# MurataBreakout_rev1.net
KiCad netlist of a schematic drawn in EAGLE
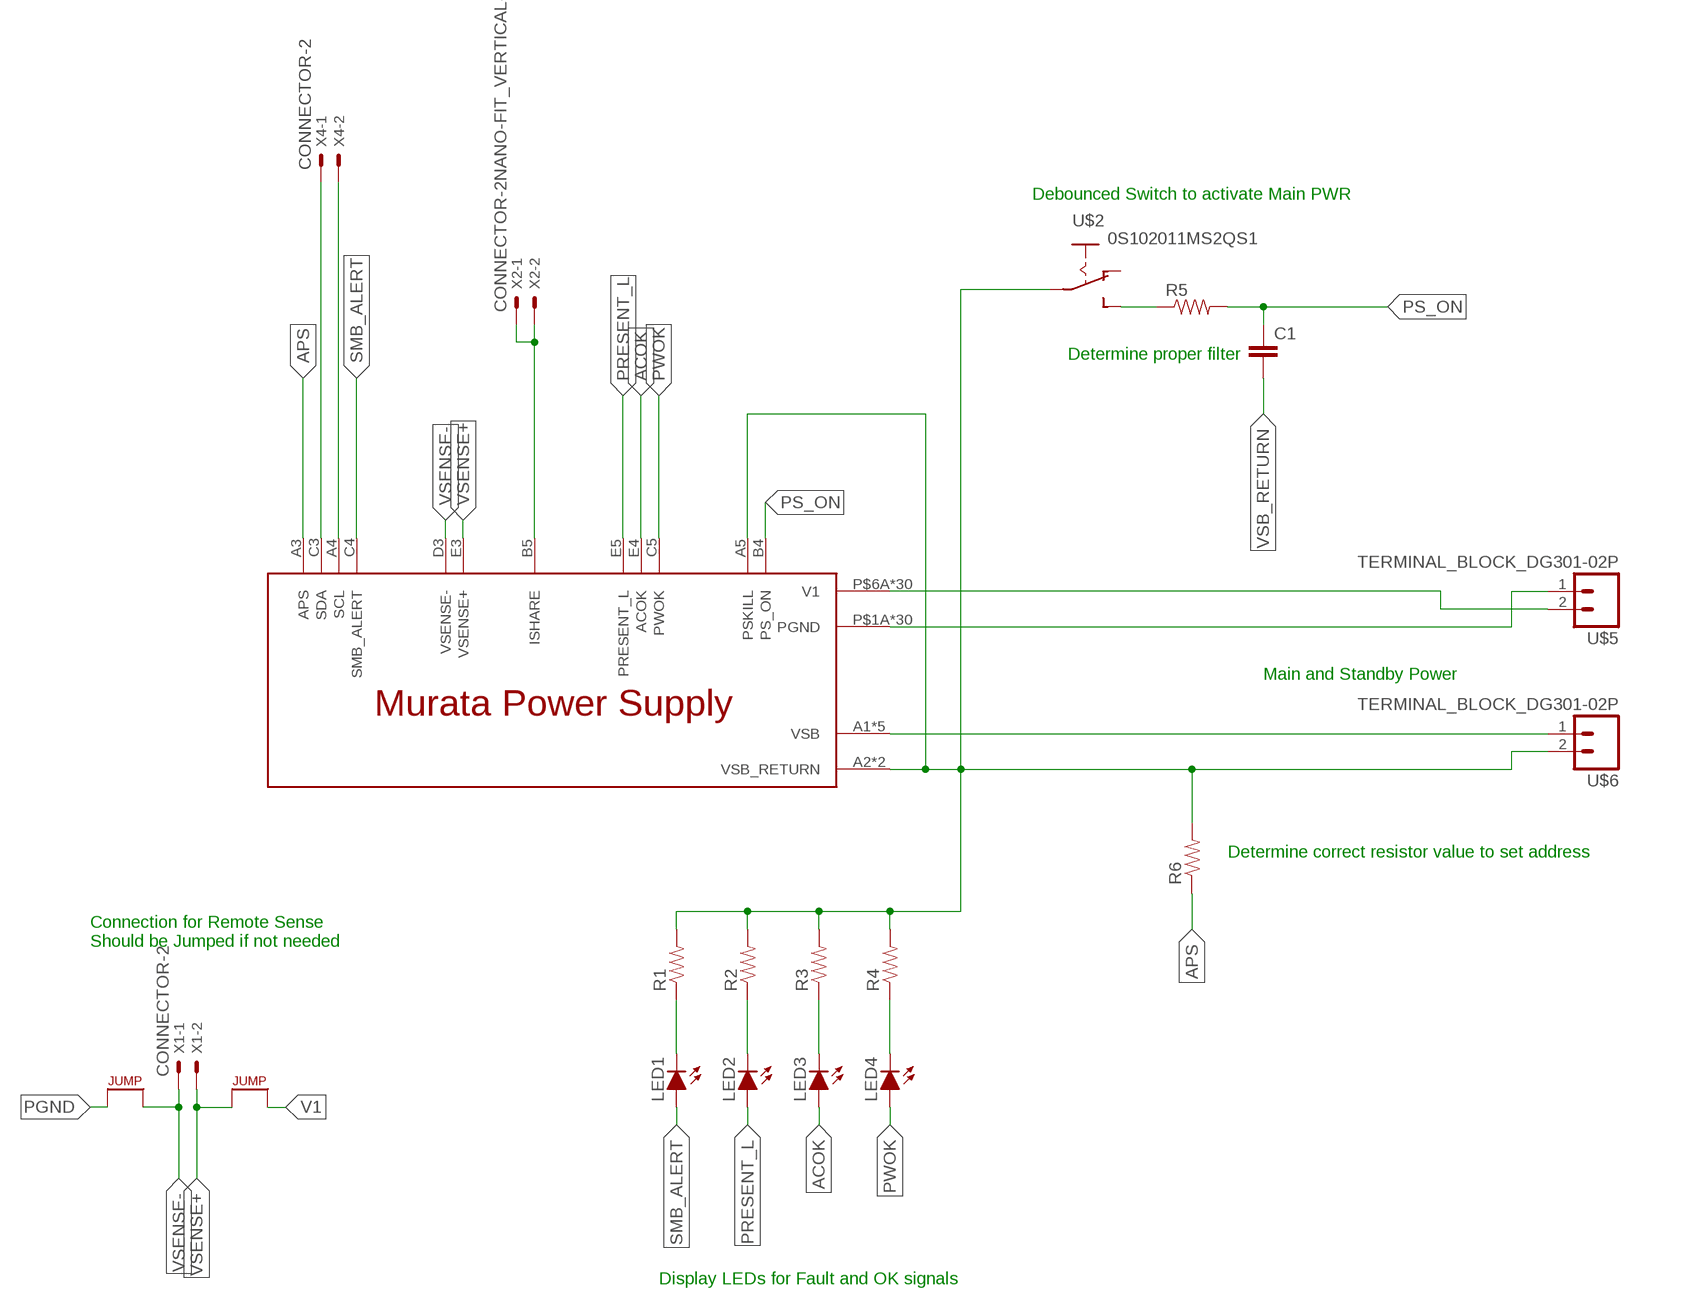
[diagram p0: schematic, sheet 1]

(export (version "E")
  (design (tool "Eeschema 10.0.6"))
  (components
    (comp (ref "C1")
      (value "CAP0805")
      (footprint "eagle-import:0805")
      (libsource (lib "eagle-import") (part "CAP0805"))
    )
    (comp (ref "LED1")
      (value "LED-0805")
      (footprint "eagle-import:LED-805")
      (libsource (lib "eagle-import") (part "LED-0805"))
    )
    (comp (ref "LED2")
      (value "LED-0805")
      (footprint "eagle-import:LED-805")
      (libsource (lib "eagle-import") (part "LED-0805"))
    )
    (comp (ref "LED3")
      (value "LED-0805")
      (footprint "eagle-import:LED-805")
      (libsource (lib "eagle-import") (part "LED-0805"))
    )
    (comp (ref "LED4")
      (value "LED-0805")
      (footprint "eagle-import:LED-805")
      (libsource (lib "eagle-import") (part "LED-0805"))
    )
    (comp (ref "R1")
      (value "RESISTOR0805-RES")
      (footprint "eagle-import:0805")
      (libsource (lib "eagle-import") (part "RESISTOR0805-RES"))
    )
    (comp (ref "R2")
      (value "RESISTOR0805-RES")
      (footprint "eagle-import:0805")
      (libsource (lib "eagle-import") (part "RESISTOR0805-RES"))
    )
    (comp (ref "R3")
      (value "RESISTOR0805-RES")
      (footprint "eagle-import:0805")
      (libsource (lib "eagle-import") (part "RESISTOR0805-RES"))
    )
    (comp (ref "R4")
      (value "RESISTOR0805-RES")
      (footprint "eagle-import:0805")
      (libsource (lib "eagle-import") (part "RESISTOR0805-RES"))
    )
    (comp (ref "R5")
      (value "RESISTOR0805-RES")
      (footprint "eagle-import:0805")
      (libsource (lib "eagle-import") (part "RESISTOR0805-RES"))
    )
    (comp (ref "R6")
      (value "RESISTOR0805-RES")
      (footprint "eagle-import:0805")
      (libsource (lib "eagle-import") (part "RESISTOR0805-RES"))
    )
    (comp (ref "U$1")
      (value "MURATA_POWER_SUPPLY")
      (footprint "eagle-import:MURATA_POWER_SUPPLY_CONNECTOR")
      (libsource (lib "eagle-import") (part "MURATA_POWER_SUPPLY"))
    )
    (comp (ref "U$2")
      (value "0S102011MS2QS1")
      (footprint "eagle-import:0S102011MS2QS1")
      (libsource (lib "eagle-import") (part "0S102011MS2QS1"))
    )
    (comp (ref "U$3")
      (value "JUMPER.1")
      (footprint "eagle-import:1X02")
      (libsource (lib "eagle-import") (part "JUMPER.1"))
    )
    (comp (ref "U$4")
      (value "JUMPER.1")
      (footprint "eagle-import:1X02")
      (libsource (lib "eagle-import") (part "JUMPER.1"))
    )
    (comp (ref "U$5")
      (value "TERMINAL_BLOCK_DG301-02P")
      (footprint "eagle-import:DG301-02P")
      (libsource (lib "eagle-import") (part "TERMINAL_BLOCK_DG301-02P"))
    )
    (comp (ref "U$6")
      (value "TERMINAL_BLOCK_DG301-02P")
      (footprint "eagle-import:DG301-02P")
      (libsource (lib "eagle-import") (part "TERMINAL_BLOCK_DG301-02P"))
    )
    (comp (ref "X1")
      (value "CONNECTOR-2")
      (footprint "eagle-import:MINIFIT_5566-2")
      (libsource (lib "eagle-import") (part "CONNECTOR-2"))
    )
    (comp (ref "X2")
      (value "CONNECTOR-2NANO-FIT_VERTICAL-2")
      (footprint "eagle-import:NANO-FIT_VERTICAL-2")
      (libsource (lib "eagle-import") (part "CONNECTOR-2NANO-FIT_VERTICAL-2"))
    )
    (comp (ref "X4")
      (value "CONNECTOR-2")
      (footprint "eagle-import:MINIFIT_5566-2")
      (libsource (lib "eagle-import") (part "CONNECTOR-2"))
    )
  )
  (nets
    (net (code "1") (name "ACOK") (class "Default")
      (node (ref "LED3") (pin "A") (pinfunction "A_A") (pintype "passive"))
      (node (ref "U$1") (pin "E4") (pinfunction "ACOK_E4") (pintype "bidirectional"))
    )
    (net (code "2") (name "APS") (class "Default")
      (node (ref "R6") (pin "1") (pinfunction "1_1") (pintype "passive"))
      (node (ref "U$1") (pin "A3") (pinfunction "APS_A3") (pintype "bidirectional"))
    )
    (net (code "3") (name "Net-(LED1-PadC)") (class "Default")
      (node (ref "LED1") (pin "C") (pinfunction "C_C") (pintype "passive"))
      (node (ref "R1") (pin "1") (pinfunction "1_1") (pintype "passive"))
    )
    (net (code "4") (name "Net-(LED2-PadC)") (class "Default")
      (node (ref "LED2") (pin "C") (pinfunction "C_C") (pintype "passive"))
      (node (ref "R2") (pin "1") (pinfunction "1_1") (pintype "passive"))
    )
    (net (code "5") (name "Net-(LED3-PadC)") (class "Default")
      (node (ref "LED3") (pin "C") (pinfunction "C_C") (pintype "passive"))
      (node (ref "R3") (pin "1") (pinfunction "1_1") (pintype "passive"))
    )
    (net (code "6") (name "Net-(LED4-PadC)") (class "Default")
      (node (ref "LED4") (pin "C") (pinfunction "C_C") (pintype "passive"))
      (node (ref "R4") (pin "1") (pinfunction "1_1") (pintype "passive"))
    )
    (net (code "7") (name "Net-(U$1-ISHARE)") (class "Default")
      (node (ref "U$1") (pin "B5") (pinfunction "ISHARE_B5") (pintype "bidirectional"))
      (node (ref "X2") (pin "P$1") (pinfunction "S_P$1") (pintype "passive"))
      (node (ref "X2") (pin "P$2") (pinfunction "S_P$2") (pintype "passive"))
    )
    (net (code "8") (name "Net-(U$1-SCL)") (class "Default")
      (node (ref "U$1") (pin "A4") (pinfunction "SCL_A4") (pintype "bidirectional"))
      (node (ref "X4") (pin "2") (pinfunction "S_2") (pintype "passive"))
    )
    (net (code "9") (name "Net-(U$1-SDA)") (class "Default")
      (node (ref "U$1") (pin "C3") (pinfunction "SDA_C3") (pintype "bidirectional"))
      (node (ref "X4") (pin "1") (pinfunction "S_1") (pintype "passive"))
    )
    (net (code "10") (name "Net-(U$1-VSB-PadA1)") (class "Default")
      (node (ref "U$1") (pin "A1") (pinfunction "VSB_A1") (pintype "bidirectional"))
      (node (ref "U$1") (pin "B1") (pinfunction "VSB_B1") (pintype "bidirectional"))
      (node (ref "U$1") (pin "C1") (pinfunction "VSB_C1") (pintype "bidirectional"))
      (node (ref "U$1") (pin "D1") (pinfunction "VSB_D1") (pintype "bidirectional"))
      (node (ref "U$1") (pin "E1") (pinfunction "VSB_E1") (pintype "bidirectional"))
      (node (ref "U$6") (pin "1") (pinfunction "1_1") (pintype "passive"))
    )
    (net (code "11") (name "Net-(U$2-S)") (class "Default")
      (node (ref "R5") (pin "1") (pinfunction "1_1") (pintype "passive"))
      (node (ref "U$2") (pin "P$3") (pinfunction "S_P$3") (pintype "passive"))
    )
    (net (code "12") (name "PGND") (class "Default")
      (node (ref "U$1") (pin "P$1A") (pinfunction "PGND_P$1A") (pintype "bidirectional"))
      (node (ref "U$1") (pin "P$1B") (pinfunction "PGND_P$1B") (pintype "bidirectional"))
      (node (ref "U$1") (pin "P$1C") (pinfunction "PGND_P$1C") (pintype "bidirectional"))
      (node (ref "U$1") (pin "P$1D") (pinfunction "PGND_P$1D") (pintype "bidirectional"))
      (node (ref "U$1") (pin "P$1E") (pinfunction "PGND_P$1E") (pintype "bidirectional"))
      (node (ref "U$1") (pin "P$1F") (pinfunction "PGND_P$1F") (pintype "bidirectional"))
      (node (ref "U$1") (pin "P$2A") (pinfunction "PGND_P$2A") (pintype "bidirectional"))
      (node (ref "U$1") (pin "P$2B") (pinfunction "PGND_P$2B") (pintype "bidirectional"))
      (node (ref "U$1") (pin "P$2C") (pinfunction "PGND_P$2C") (pintype "bidirectional"))
      (node (ref "U$1") (pin "P$2D") (pinfunction "PGND_P$2D") (pintype "bidirectional"))
      (node (ref "U$1") (pin "P$2E") (pinfunction "PGND_P$2E") (pintype "bidirectional"))
      (node (ref "U$1") (pin "P$2F") (pinfunction "PGND_P$2F") (pintype "bidirectional"))
      (node (ref "U$1") (pin "P$3A") (pinfunction "PGND_P$3A") (pintype "bidirectional"))
      (node (ref "U$1") (pin "P$3B") (pinfunction "PGND_P$3B") (pintype "bidirectional"))
      (node (ref "U$1") (pin "P$3C") (pinfunction "PGND_P$3C") (pintype "bidirectional"))
      (node (ref "U$1") (pin "P$3D") (pinfunction "PGND_P$3D") (pintype "bidirectional"))
      (node (ref "U$1") (pin "P$3E") (pinfunction "PGND_P$3E") (pintype "bidirectional"))
      (node (ref "U$1") (pin "P$3F") (pinfunction "PGND_P$3F") (pintype "bidirectional"))
      (node (ref "U$1") (pin "P$4A") (pinfunction "PGND_P$4A") (pintype "bidirectional"))
      (node (ref "U$1") (pin "P$4B") (pinfunction "PGND_P$4B") (pintype "bidirectional"))
      (node (ref "U$1") (pin "P$4C") (pinfunction "PGND_P$4C") (pintype "bidirectional"))
      (node (ref "U$1") (pin "P$4D") (pinfunction "PGND_P$4D") (pintype "bidirectional"))
      (node (ref "U$1") (pin "P$4E") (pinfunction "PGND_P$4E") (pintype "bidirectional"))
      (node (ref "U$1") (pin "P$4F") (pinfunction "PGND_P$4F") (pintype "bidirectional"))
      (node (ref "U$1") (pin "P$5A") (pinfunction "PGND_P$5A") (pintype "bidirectional"))
      (node (ref "U$1") (pin "P$5B") (pinfunction "PGND_P$5B") (pintype "bidirectional"))
      (node (ref "U$1") (pin "P$5C") (pinfunction "PGND_P$5C") (pintype "bidirectional"))
      (node (ref "U$1") (pin "P$5D") (pinfunction "PGND_P$5D") (pintype "bidirectional"))
      (node (ref "U$1") (pin "P$5E") (pinfunction "PGND_P$5E") (pintype "bidirectional"))
      (node (ref "U$1") (pin "P$5F") (pinfunction "PGND_P$5F") (pintype "bidirectional"))
      (node (ref "U$4") (pin "1") (pinfunction "P$1_1") (pintype "bidirectional"))
      (node (ref "U$5") (pin "1") (pinfunction "1_1") (pintype "passive"))
    )
    (net (code "13") (name "PRESENT_L") (class "Default")
      (node (ref "LED2") (pin "A") (pinfunction "A_A") (pintype "passive"))
      (node (ref "U$1") (pin "E5") (pinfunction "PRESENT_L_E5") (pintype "bidirectional"))
    )
    (net (code "14") (name "PS_ON") (class "Default")
      (node (ref "C1") (pin "1") (pinfunction "1_1") (pintype "passive"))
      (node (ref "R5") (pin "2") (pinfunction "2_2") (pintype "passive"))
      (node (ref "U$1") (pin "B4") (pinfunction "PS_ON_B4") (pintype "bidirectional"))
    )
    (net (code "15") (name "PWOK") (class "Default")
      (node (ref "LED4") (pin "A") (pinfunction "A_A") (pintype "passive"))
      (node (ref "U$1") (pin "C5") (pinfunction "PWOK_C5") (pintype "bidirectional"))
    )
    (net (code "16") (name "SMB_ALERT") (class "Default")
      (node (ref "LED1") (pin "A") (pinfunction "A_A") (pintype "passive"))
      (node (ref "U$1") (pin "C4") (pinfunction "SMB_ALERT_C4") (pintype "bidirectional"))
    )
    (net (code "17") (name "V1") (class "Default")
      (node (ref "U$1") (pin "P$10A") (pinfunction "V1_P$10A") (pintype "bidirectional"))
      (node (ref "U$1") (pin "P$10B") (pinfunction "V1_P$10B") (pintype "bidirectional"))
      (node (ref "U$1") (pin "P$10C") (pinfunction "V1_P$10C") (pintype "bidirectional"))
      (node (ref "U$1") (pin "P$10D") (pinfunction "V1_P$10D") (pintype "bidirectional"))
      (node (ref "U$1") (pin "P$10E") (pinfunction "V1_P$10E") (pintype "bidirectional"))
      (node (ref "U$1") (pin "P$10F") (pinfunction "V1_P$10F") (pintype "bidirectional"))
      (node (ref "U$1") (pin "P$6A") (pinfunction "V1_P$6A") (pintype "bidirectional"))
      (node (ref "U$1") (pin "P$6B") (pinfunction "V1_P$6B") (pintype "bidirectional"))
      (node (ref "U$1") (pin "P$6C") (pinfunction "V1_P$6C") (pintype "bidirectional"))
      (node (ref "U$1") (pin "P$6D") (pinfunction "V1_P$6D") (pintype "bidirectional"))
      (node (ref "U$1") (pin "P$6E") (pinfunction "V1_P$6E") (pintype "bidirectional"))
      (node (ref "U$1") (pin "P$6F") (pinfunction "V1_P$6F") (pintype "bidirectional"))
      (node (ref "U$1") (pin "P$7A") (pinfunction "V1_P$7A") (pintype "bidirectional"))
      (node (ref "U$1") (pin "P$7B") (pinfunction "V1_P$7B") (pintype "bidirectional"))
      (node (ref "U$1") (pin "P$7C") (pinfunction "V1_P$7C") (pintype "bidirectional"))
      (node (ref "U$1") (pin "P$7D") (pinfunction "V1_P$7D") (pintype "bidirectional"))
      (node (ref "U$1") (pin "P$7E") (pinfunction "V1_P$7E") (pintype "bidirectional"))
      (node (ref "U$1") (pin "P$7F") (pinfunction "V1_P$7F") (pintype "bidirectional"))
      (node (ref "U$1") (pin "P$8A") (pinfunction "V1_P$8A") (pintype "bidirectional"))
      (node (ref "U$1") (pin "P$8B") (pinfunction "V1_P$8B") (pintype "bidirectional"))
      (node (ref "U$1") (pin "P$8C") (pinfunction "V1_P$8C") (pintype "bidirectional"))
      (node (ref "U$1") (pin "P$8D") (pinfunction "V1_P$8D") (pintype "bidirectional"))
      (node (ref "U$1") (pin "P$8E") (pinfunction "V1_P$8E") (pintype "bidirectional"))
      (node (ref "U$1") (pin "P$8F") (pinfunction "V1_P$8F") (pintype "bidirectional"))
      (node (ref "U$1") (pin "P$9A") (pinfunction "V1_P$9A") (pintype "bidirectional"))
      (node (ref "U$1") (pin "P$9B") (pinfunction "V1_P$9B") (pintype "bidirectional"))
      (node (ref "U$1") (pin "P$9C") (pinfunction "V1_P$9C") (pintype "bidirectional"))
      (node (ref "U$1") (pin "P$9D") (pinfunction "V1_P$9D") (pintype "bidirectional"))
      (node (ref "U$1") (pin "P$9E") (pinfunction "V1_P$9E") (pintype "bidirectional"))
      (node (ref "U$1") (pin "P$9F") (pinfunction "V1_P$9F") (pintype "bidirectional"))
      (node (ref "U$3") (pin "2") (pinfunction "P$2_2") (pintype "bidirectional"))
      (node (ref "U$5") (pin "2") (pinfunction "2_2") (pintype "passive"))
    )
    (net (code "18") (name "VSB_RETURN") (class "Default")
      (node (ref "C1") (pin "2") (pinfunction "2_2") (pintype "passive"))
      (node (ref "R1") (pin "2") (pinfunction "2_2") (pintype "passive"))
      (node (ref "R2") (pin "2") (pinfunction "2_2") (pintype "passive"))
      (node (ref "R3") (pin "2") (pinfunction "2_2") (pintype "passive"))
      (node (ref "R4") (pin "2") (pinfunction "2_2") (pintype "passive"))
      (node (ref "R6") (pin "2") (pinfunction "2_2") (pintype "passive"))
      (node (ref "U$1") (pin "A2") (pinfunction "VSB_RETURN_A2") (pintype "bidirectional"))
      (node (ref "U$1") (pin "A5") (pinfunction "PSKILL_A5") (pintype "bidirectional"))
      (node (ref "U$1") (pin "B2") (pinfunction "VSB_RETURN_B2") (pintype "bidirectional"))
      (node (ref "U$2") (pin "P$2") (pinfunction "P_P$2") (pintype "passive"))
      (node (ref "U$6") (pin "2") (pinfunction "2_2") (pintype "passive"))
    )
    (net (code "19") (name "VSENSE+") (class "Default")
      (node (ref "U$1") (pin "E3") (pinfunction "VSENSE+_E3") (pintype "bidirectional"))
      (node (ref "U$3") (pin "1") (pinfunction "P$1_1") (pintype "bidirectional"))
      (node (ref "X1") (pin "2") (pinfunction "S_2") (pintype "passive"))
    )
    (net (code "20") (name "VSENSE-") (class "Default")
      (node (ref "U$1") (pin "D3") (pinfunction "VSENSE-_D3") (pintype "bidirectional"))
      (node (ref "U$4") (pin "2") (pinfunction "P$2_2") (pintype "bidirectional"))
      (node (ref "X1") (pin "1") (pinfunction "S_1") (pintype "passive"))
    )
    (net (code "21") (name "unconnected-(U$2-O-PadP$1)") (class "Default")
      (node (ref "U$2") (pin "P$1") (pinfunction "O_P$1") (pintype "passive"))
    )
  )
)
